# PRoMo_Base_DIP_v1_1.net
KiCad netlist of a schematic drawn in EAGLE
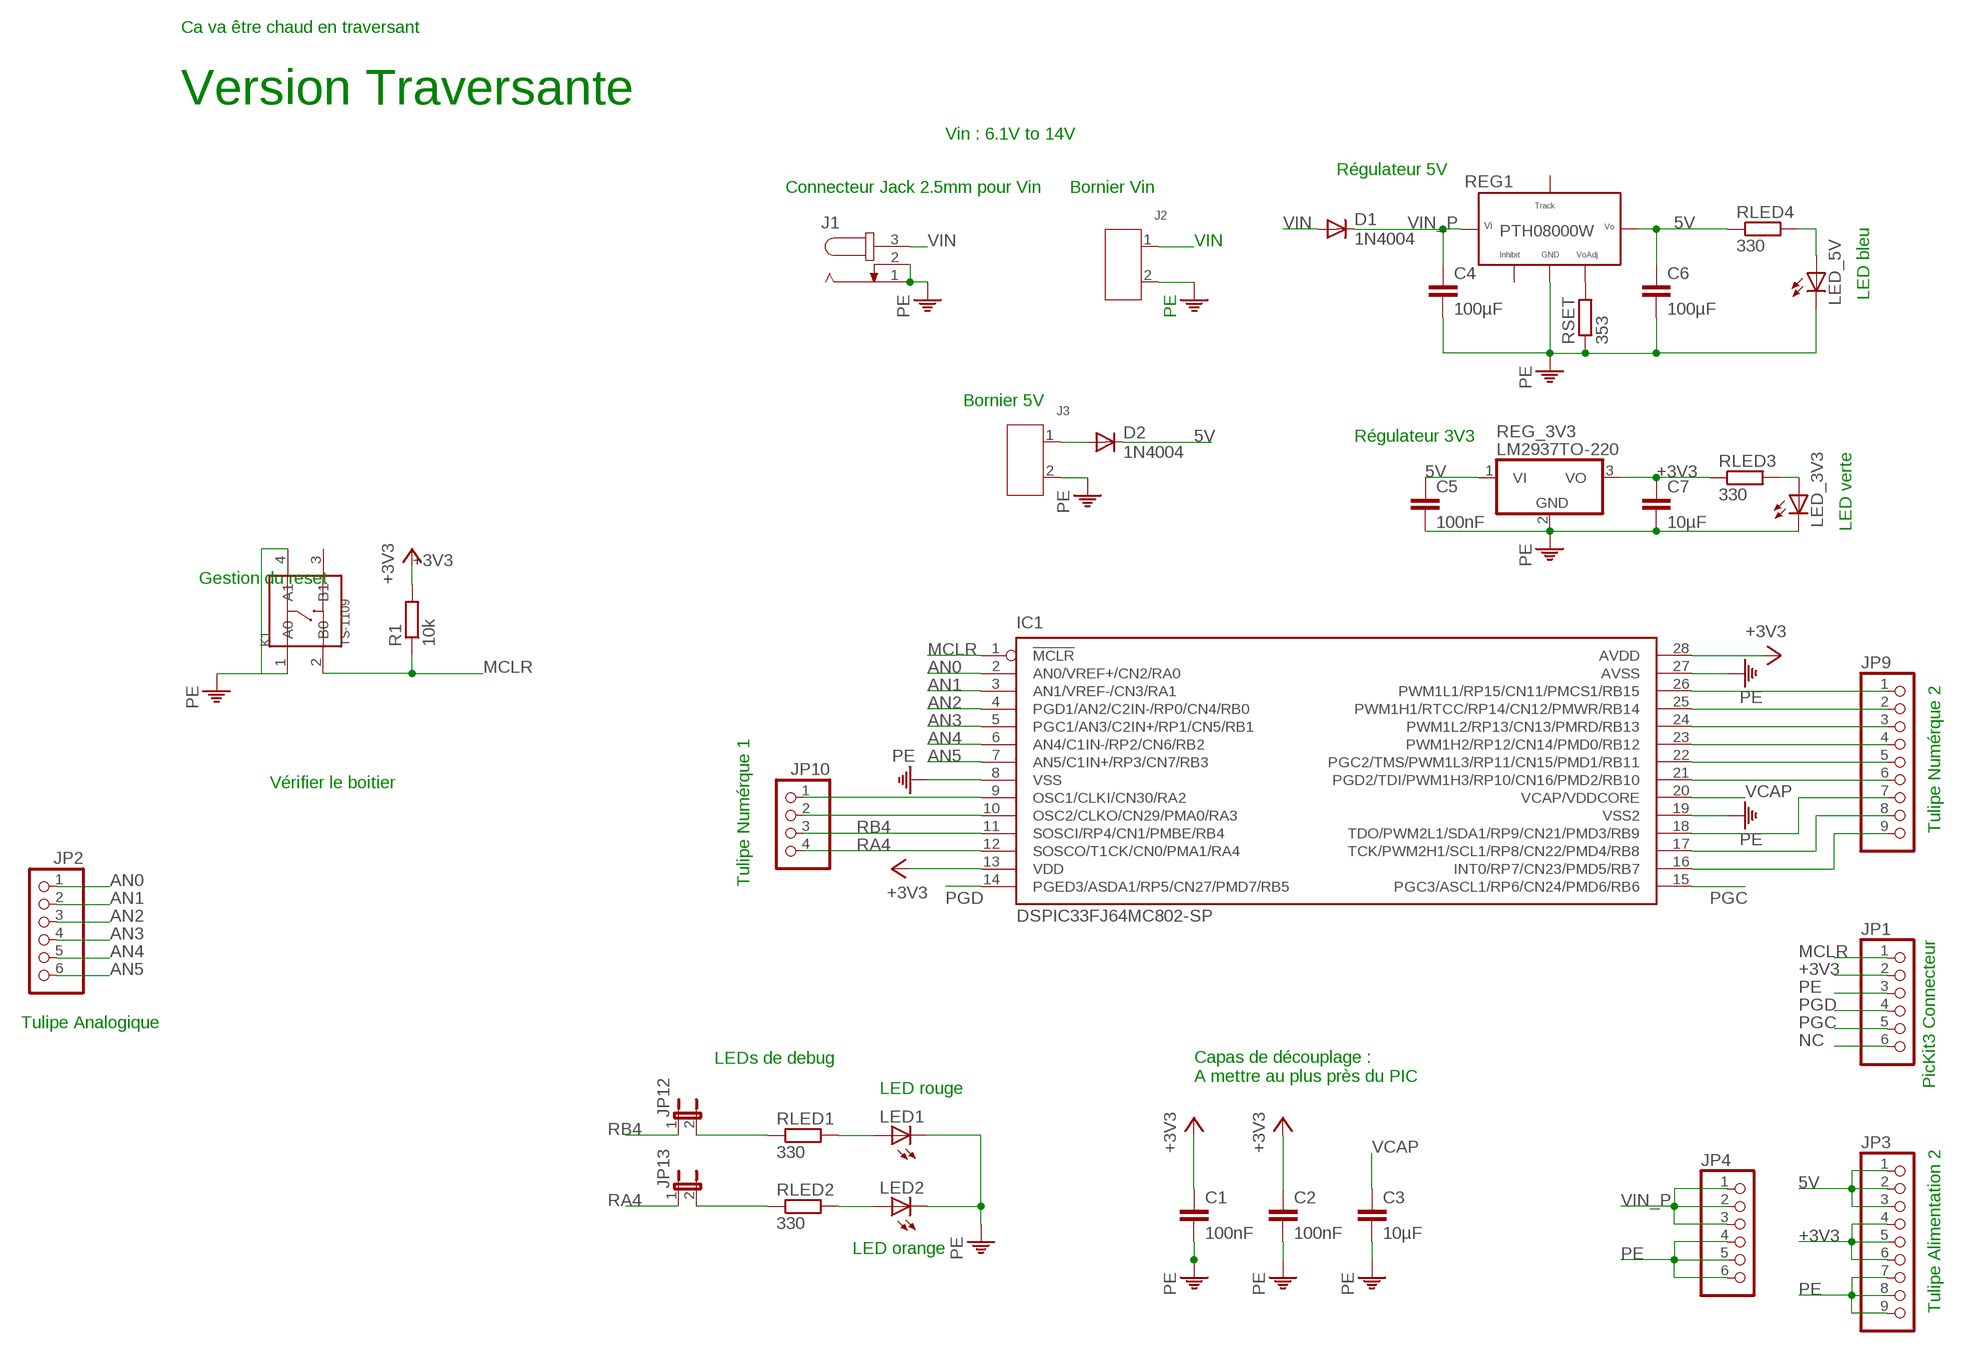
[diagram p0: schematic, sheet 1]

(export (version "E")
  (design (tool "Eeschema 10.0.6"))
  (components
    (comp (ref "C1")
      (value "100nF")
      (footprint "eagle-import:C102-043X133")
      (libsource (lib "eagle-import") (part "C-EU102-043X133"))
    )
    (comp (ref "C2")
      (value "100nF")
      (footprint "eagle-import:C050-035X075")
      (libsource (lib "eagle-import") (part "C-EU050-035X075"))
    )
    (comp (ref "C3")
      (value "10µF")
      (footprint "eagle-import:C050-035X075")
      (libsource (lib "eagle-import") (part "C-EU050-035X075"))
    )
    (comp (ref "C4")
      (value "100µF")
      (footprint "eagle-import:C050-035X075")
      (libsource (lib "eagle-import") (part "C-EU050-035X075"))
    )
    (comp (ref "C5")
      (value "100nF")
      (footprint "eagle-import:C050-035X075")
      (libsource (lib "eagle-import") (part "C-EU050-035X075"))
    )
    (comp (ref "C6")
      (value "100µF")
      (footprint "eagle-import:C050-035X075")
      (libsource (lib "eagle-import") (part "C-EU050-035X075"))
    )
    (comp (ref "C7")
      (value "10µF")
      (footprint "eagle-import:C050-035X075")
      (libsource (lib "eagle-import") (part "C-EU050-035X075"))
    )
    (comp (ref "D1")
      (value "1N4004")
      (footprint "eagle-import:DO41-10")
      (libsource (lib "eagle-import") (part "1N4004"))
    )
    (comp (ref "D2")
      (value "1N4004")
      (footprint "eagle-import:DO41-10")
      (libsource (lib "eagle-import") (part "1N4004"))
    )
    (comp (ref "IC1")
      (value "DSPIC33FJ64MC802-SP")
      (footprint "eagle-import:DIL28-3")
      (libsource (lib "eagle-import") (part "DSPIC33FJ64MC802-SP"))
    )
    (comp (ref "J1")
      (value "JACK-PLUG1")
      (footprint "eagle-import:SPC4078")
      (libsource (lib "eagle-import") (part "JACK-PLUG1"))
    )
    (comp (ref "J2")
      (value "SCREW-TERMINAL-GREEN(2P-5.0)")
      (footprint "eagle-import:H2-5.0-10.5X8.0MM")
      (libsource (lib "eagle-import") (part "SCREW-TERMINAL-GREEN(2P-5.0)"))
    )
    (comp (ref "J3")
      (value "SCREW-TERMINAL-GREEN(2P-5.0)")
      (footprint "eagle-import:H2-5.0-10.5X8.0MM")
      (libsource (lib "eagle-import") (part "SCREW-TERMINAL-GREEN(2P-5.0)"))
    )
    (comp (ref "JP1")
      (value "PINHD-1X6/90")
      (footprint "eagle-import:1X06_90")
      (libsource (lib "eagle-import") (part "PINHD-1X6/90"))
    )
    (comp (ref "JP2")
      (value "PINHD-1X6")
      (footprint "eagle-import:1X06")
      (libsource (lib "eagle-import") (part "PINHD-1X6"))
    )
    (comp (ref "JP3")
      (value "PINHD-1X9")
      (footprint "eagle-import:1X09")
      (libsource (lib "eagle-import") (part "PINHD-1X9"))
    )
    (comp (ref "JP4")
      (value "PINHD-1X6")
      (footprint "eagle-import:1X06")
      (libsource (lib "eagle-import") (part "PINHD-1X6"))
    )
    (comp (ref "JP9")
      (value "PINHD-1X9")
      (footprint "eagle-import:1X09")
      (libsource (lib "eagle-import") (part "PINHD-1X9"))
    )
    (comp (ref "JP10")
      (value "PINHD-1X4")
      (footprint "eagle-import:1X04")
      (libsource (lib "eagle-import") (part "PINHD-1X4"))
    )
    (comp (ref "JP12")
      (value "JP1E")
      (footprint "eagle-import:JP1")
      (libsource (lib "eagle-import") (part "JP1E"))
    )
    (comp (ref "JP13")
      (value "JP1E")
      (footprint "eagle-import:JP1")
      (libsource (lib "eagle-import") (part "JP1E"))
    )
    (comp (ref "K1")
      (value "TS-1109")
      (footprint "eagle-import:SW4-6.0X6.0X5.0MM")
      (libsource (lib "eagle-import") (part "DIP-BUTTON-4P"))
    )
    (comp (ref "LED1")
      (value "LED3MM")
      (footprint "eagle-import:LED3MM")
      (libsource (lib "eagle-import") (part "LED3MM"))
    )
    (comp (ref "LED2")
      (value "LED3MM")
      (footprint "eagle-import:LED3MM")
      (libsource (lib "eagle-import") (part "LED3MM"))
    )
    (comp (ref "LED_3V3")
      (value "LED3MM")
      (footprint "eagle-import:LED3MM")
      (libsource (lib "eagle-import") (part "LED3MM"))
    )
    (comp (ref "LED_5V")
      (value "LED3MM")
      (footprint "eagle-import:LED3MM")
      (libsource (lib "eagle-import") (part "LED3MM"))
    )
    (comp (ref "R1")
      (value "10k")
      (footprint "eagle-import:0207_10")
      (libsource (lib "eagle-import") (part "R-EU_0207/10"))
    )
    (comp (ref "REG1")
      (value "PTH08000W(EUS)")
      (footprint "eagle-import:TRHOUGH_HOLE_(EUS)")
      (libsource (lib "eagle-import") (part "PTH08000W(EUS)"))
    )
    (comp (ref "REG_3V3")
      (value "LM2937TO-220")
      (footprint "eagle-import:TO220V")
      (libsource (lib "eagle-import") (part "LM2937TO-220"))
    )
    (comp (ref "RLED1")
      (value "330")
      (footprint "eagle-import:0207_10")
      (libsource (lib "eagle-import") (part "R-EU_0207/10"))
    )
    (comp (ref "RLED2")
      (value "330")
      (footprint "eagle-import:0207_10")
      (libsource (lib "eagle-import") (part "R-EU_0207/10"))
    )
    (comp (ref "RLED3")
      (value "330")
      (footprint "eagle-import:0207_10")
      (libsource (lib "eagle-import") (part "R-EU_0207/10"))
    )
    (comp (ref "RLED4")
      (value "330")
      (footprint "eagle-import:0207_10")
      (libsource (lib "eagle-import") (part "R-EU_0207/10"))
    )
    (comp (ref "RSET")
      (value "353")
      (footprint "eagle-import:0207_10")
      (libsource (lib "eagle-import") (part "R-EU_0207/10"))
    )
  )
  (nets
    (net (code "1") (name "+3V3") (class "Default")
      (node (ref "C1") (pin "1") (pinfunction "1_1") (pintype "passive"))
      (node (ref "C2") (pin "1") (pinfunction "1_1") (pintype "passive"))
      (node (ref "C7") (pin "1") (pinfunction "1_1") (pintype "passive"))
      (node (ref "IC1") (pin "13") (pinfunction "VDD_13") (pintype "power_in"))
      (node (ref "IC1") (pin "28") (pinfunction "AVDD_28") (pintype "power_in"))
      (node (ref "JP1") (pin "2") (pinfunction "2_2") (pintype "passive"))
      (node (ref "JP3") (pin "4") (pinfunction "4_4") (pintype "passive"))
      (node (ref "JP3") (pin "5") (pinfunction "5_5") (pintype "passive"))
      (node (ref "JP3") (pin "6") (pinfunction "6_6") (pintype "passive"))
      (node (ref "R1") (pin "2") (pinfunction "2_2") (pintype "passive"))
      (node (ref "REG_3V3") (pin "3") (pinfunction "VO_3") (pintype "passive"))
      (node (ref "RLED3") (pin "1") (pinfunction "1_1") (pintype "passive"))
    )
    (net (code "2") (name "/5V") (class "Default")
      (node (ref "C5") (pin "1") (pinfunction "1_1") (pintype "passive"))
      (node (ref "C6") (pin "1") (pinfunction "1_1") (pintype "passive"))
      (node (ref "D2") (pin "C") (pinfunction "C_C") (pintype "passive"))
      (node (ref "JP3") (pin "1") (pinfunction "1_1") (pintype "passive"))
      (node (ref "JP3") (pin "2") (pinfunction "2_2") (pintype "passive"))
      (node (ref "JP3") (pin "3") (pinfunction "3_3") (pintype "passive"))
      (node (ref "REG1") (pin "6") (pinfunction "6_6") (pintype "bidirectional"))
      (node (ref "REG_3V3") (pin "1") (pinfunction "VI_1") (pintype "input"))
      (node (ref "RLED4") (pin "1") (pinfunction "1_1") (pintype "passive"))
    )
    (net (code "3") (name "/AN0") (class "Default")
      (node (ref "IC1") (pin "2") (pinfunction "AN0/VREF+/CN2/RA0_2") (pintype "bidirectional"))
      (node (ref "JP2") (pin "1") (pinfunction "1_1") (pintype "passive"))
    )
    (net (code "4") (name "/AN1") (class "Default")
      (node (ref "IC1") (pin "3") (pinfunction "AN1/VREF-/CN3/RA1_3") (pintype "bidirectional"))
      (node (ref "JP2") (pin "2") (pinfunction "2_2") (pintype "passive"))
    )
    (net (code "5") (name "/AN2") (class "Default")
      (node (ref "IC1") (pin "4") (pinfunction "PGD1/AN2/C2IN-/RP0/CN4/RB0_4") (pintype "bidirectional"))
      (node (ref "JP2") (pin "3") (pinfunction "3_3") (pintype "passive"))
    )
    (net (code "6") (name "/AN3") (class "Default")
      (node (ref "IC1") (pin "5") (pinfunction "PGC1/AN3/C2IN+/RP1/CN5/RB1_5") (pintype "bidirectional"))
      (node (ref "JP2") (pin "4") (pinfunction "4_4") (pintype "passive"))
    )
    (net (code "7") (name "/AN4") (class "Default")
      (node (ref "IC1") (pin "6") (pinfunction "AN4/C1IN-/RP2/CN6/RB2_6") (pintype "bidirectional"))
      (node (ref "JP2") (pin "5") (pinfunction "5_5") (pintype "passive"))
    )
    (net (code "8") (name "/AN5") (class "Default")
      (node (ref "IC1") (pin "7") (pinfunction "AN5/C1IN+/RP3/CN7/RB3_7") (pintype "bidirectional"))
      (node (ref "JP2") (pin "6") (pinfunction "6_6") (pintype "passive"))
    )
    (net (code "9") (name "/MCLR") (class "Default")
      (node (ref "IC1") (pin "1") (pinfunction "~{MCLR}_1") (pintype "input"))
      (node (ref "JP1") (pin "1") (pinfunction "1_1") (pintype "passive"))
      (node (ref "K1") (pin "2") (pinfunction "B0_2") (pintype "bidirectional"))
      (node (ref "R1") (pin "1") (pinfunction "1_1") (pintype "passive"))
    )
    (net (code "10") (name "/NC") (class "Default")
      (node (ref "JP1") (pin "6") (pinfunction "6_6") (pintype "passive"))
    )
    (net (code "11") (name "/PGC") (class "Default")
      (node (ref "IC1") (pin "15") (pinfunction "PGC3/ASCL1/RP6/CN24/PMD6/RB6_15") (pintype "bidirectional"))
      (node (ref "JP1") (pin "5") (pinfunction "5_5") (pintype "passive"))
    )
    (net (code "12") (name "/PGD") (class "Default")
      (node (ref "IC1") (pin "14") (pinfunction "PGED3/ASDA1/RP5/CN27/PMD7/RB5_14") (pintype "bidirectional"))
      (node (ref "JP1") (pin "4") (pinfunction "4_4") (pintype "passive"))
    )
    (net (code "13") (name "/RA4") (class "Default")
      (node (ref "IC1") (pin "12") (pinfunction "SOSCO/T1CK/CN0/PMA1/RA4_12") (pintype "bidirectional"))
      (node (ref "JP10") (pin "4") (pinfunction "4_4") (pintype "passive"))
      (node (ref "JP13") (pin "1") (pinfunction "1_1") (pintype "passive"))
    )
    (net (code "14") (name "/RB4") (class "Default")
      (node (ref "IC1") (pin "11") (pinfunction "SOSCI/RP4/CN1/PMBE/RB4_11") (pintype "bidirectional"))
      (node (ref "JP10") (pin "3") (pinfunction "3_3") (pintype "passive"))
      (node (ref "JP12") (pin "1") (pinfunction "1_1") (pintype "passive"))
    )
    (net (code "15") (name "/VCAP") (class "Default")
      (node (ref "C3") (pin "1") (pinfunction "1_1") (pintype "passive"))
      (node (ref "IC1") (pin "20") (pinfunction "VCAP/VDDCORE_20") (pintype "power_in"))
    )
    (net (code "16") (name "/VIN") (class "Default")
      (node (ref "D1") (pin "A") (pinfunction "A_A") (pintype "passive"))
      (node (ref "J1") (pin "3") (pinfunction "3_3") (pintype "passive"))
      (node (ref "J2") (pin "1") (pinfunction "1_1") (pintype "bidirectional"))
    )
    (net (code "17") (name "/VIN_P") (class "Default")
      (node (ref "C4") (pin "1") (pinfunction "1_1") (pintype "passive"))
      (node (ref "D1") (pin "C") (pinfunction "C_C") (pintype "passive"))
      (node (ref "JP4") (pin "1") (pinfunction "1_1") (pintype "passive"))
      (node (ref "JP4") (pin "2") (pinfunction "2_2") (pintype "passive"))
      (node (ref "JP4") (pin "3") (pinfunction "3_3") (pintype "passive"))
      (node (ref "REG1") (pin "3") (pinfunction "3_3") (pintype "bidirectional"))
    )
    (net (code "18") (name "Net-(D2-PadA)") (class "Default")
      (node (ref "D2") (pin "A") (pinfunction "A_A") (pintype "passive"))
      (node (ref "J3") (pin "1") (pinfunction "1_1") (pintype "bidirectional"))
    )
    (net (code "19") (name "Net-(IC1-INT0{slash}RP7{slash}CN23{slash}PMD5{slash}RB7)") (class "Default")
      (node (ref "IC1") (pin "16") (pinfunction "INT0/RP7/CN23/PMD5/RB7_16") (pintype "bidirectional"))
      (node (ref "JP9") (pin "9") (pinfunction "9_9") (pintype "passive"))
    )
    (net (code "20") (name "Net-(IC1-OSC1{slash}CLKI{slash}CN30{slash}RA2)") (class "Default")
      (node (ref "IC1") (pin "9") (pinfunction "OSC1/CLKI/CN30/RA2_9") (pintype "bidirectional"))
      (node (ref "JP10") (pin "1") (pinfunction "1_1") (pintype "passive"))
    )
    (net (code "21") (name "Net-(IC1-OSC2{slash}CLKO{slash}CN29{slash}PMA0{slash}RA3)") (class "Default")
      (node (ref "IC1") (pin "10") (pinfunction "OSC2/CLKO/CN29/PMA0/RA3_10") (pintype "bidirectional"))
      (node (ref "JP10") (pin "2") (pinfunction "2_2") (pintype "passive"))
    )
    (net (code "22") (name "Net-(IC1-PGC2{slash}TMS{slash}PWM1L3{slash}RP11{slash}CN15{slash}PMD1{slash}RB11)") (class "Default")
      (node (ref "IC1") (pin "22") (pinfunction "PGC2/TMS/PWM1L3/RP11/CN15/PMD1/RB11_22") (pintype "bidirectional"))
      (node (ref "JP9") (pin "5") (pinfunction "5_5") (pintype "passive"))
    )
    (net (code "23") (name "Net-(IC1-PGD2{slash}TDI{slash}PWM1H3{slash}RP10{slash}CN16{slash}PMD2{slash}RB10)") (class "Default")
      (node (ref "IC1") (pin "21") (pinfunction "PGD2/TDI/PWM1H3/RP10/CN16/PMD2/RB10_21") (pintype "bidirectional"))
      (node (ref "JP9") (pin "6") (pinfunction "6_6") (pintype "passive"))
    )
    (net (code "24") (name "Net-(IC1-PWM1H1{slash}RTCC{slash}RP14{slash}CN12{slash}PMWR{slash}RB14)") (class "Default")
      (node (ref "IC1") (pin "25") (pinfunction "PWM1H1/RTCC/RP14/CN12/PMWR/RB14_25") (pintype "bidirectional"))
      (node (ref "JP9") (pin "2") (pinfunction "2_2") (pintype "passive"))
    )
    (net (code "25") (name "Net-(IC1-PWM1H2{slash}RP12{slash}CN14{slash}PMD0{slash}RB12)") (class "Default")
      (node (ref "IC1") (pin "23") (pinfunction "PWM1H2/RP12/CN14/PMD0/RB12_23") (pintype "bidirectional"))
      (node (ref "JP9") (pin "4") (pinfunction "4_4") (pintype "passive"))
    )
    (net (code "26") (name "Net-(IC1-PWM1L1{slash}RP15{slash}CN11{slash}PMCS1{slash}RB15)") (class "Default")
      (node (ref "IC1") (pin "26") (pinfunction "PWM1L1/RP15/CN11/PMCS1/RB15_26") (pintype "bidirectional"))
      (node (ref "JP9") (pin "1") (pinfunction "1_1") (pintype "passive"))
    )
    (net (code "27") (name "Net-(IC1-PWM1L2{slash}RP13{slash}CN13{slash}PMRD{slash}RB13)") (class "Default")
      (node (ref "IC1") (pin "24") (pinfunction "PWM1L2/RP13/CN13/PMRD/RB13_24") (pintype "bidirectional"))
      (node (ref "JP9") (pin "3") (pinfunction "3_3") (pintype "passive"))
    )
    (net (code "28") (name "Net-(IC1-TCK{slash}PWM2H1{slash}SCL1{slash}RP8{slash}CN22{slash}PMD4{slash}RB8)") (class "Default")
      (node (ref "IC1") (pin "17") (pinfunction "TCK/PWM2H1/SCL1/RP8/CN22/PMD4/RB8_17") (pintype "bidirectional"))
      (node (ref "JP9") (pin "8") (pinfunction "8_8") (pintype "passive"))
    )
    (net (code "29") (name "Net-(IC1-TDO{slash}PWM2L1{slash}SDA1{slash}RP9{slash}CN21{slash}PMD3{slash}RB9)") (class "Default")
      (node (ref "IC1") (pin "18") (pinfunction "TDO/PWM2L1/SDA1/RP9/CN21/PMD3/RB9_18") (pintype "bidirectional"))
      (node (ref "JP9") (pin "7") (pinfunction "7_7") (pintype "passive"))
    )
    (net (code "30") (name "Net-(JP12-Pad2)") (class "Default")
      (node (ref "JP12") (pin "2") (pinfunction "2_2") (pintype "passive"))
      (node (ref "RLED1") (pin "1") (pinfunction "1_1") (pintype "passive"))
    )
    (net (code "31") (name "Net-(JP13-Pad2)") (class "Default")
      (node (ref "JP13") (pin "2") (pinfunction "2_2") (pintype "passive"))
      (node (ref "RLED2") (pin "1") (pinfunction "1_1") (pintype "passive"))
    )
    (net (code "32") (name "Net-(LED1-PadA)") (class "Default")
      (node (ref "LED1") (pin "A") (pinfunction "A_A") (pintype "passive"))
      (node (ref "RLED1") (pin "2") (pinfunction "2_2") (pintype "passive"))
    )
    (net (code "33") (name "Net-(LED2-PadA)") (class "Default")
      (node (ref "LED2") (pin "A") (pinfunction "A_A") (pintype "passive"))
      (node (ref "RLED2") (pin "2") (pinfunction "2_2") (pintype "passive"))
    )
    (net (code "34") (name "Net-(LED_3V3-PadA)") (class "Default")
      (node (ref "LED_3V3") (pin "A") (pinfunction "A_A") (pintype "passive"))
      (node (ref "RLED3") (pin "2") (pinfunction "2_2") (pintype "passive"))
    )
    (net (code "35") (name "Net-(LED_5V-PadA)") (class "Default")
      (node (ref "LED_5V") (pin "A") (pinfunction "A_A") (pintype "passive"))
      (node (ref "RLED4") (pin "2") (pinfunction "2_2") (pintype "passive"))
    )
    (net (code "36") (name "Net-(REG1-Pad5)") (class "Default")
      (node (ref "REG1") (pin "5") (pinfunction "5_5") (pintype "bidirectional"))
      (node (ref "RSET") (pin "2") (pinfunction "2_2") (pintype "passive"))
    )
    (net (code "37") (name "PE") (class "Default")
      (node (ref "C1") (pin "2") (pinfunction "2_2") (pintype "passive"))
      (node (ref "C2") (pin "2") (pinfunction "2_2") (pintype "passive"))
      (node (ref "C3") (pin "2") (pinfunction "2_2") (pintype "passive"))
      (node (ref "C4") (pin "2") (pinfunction "2_2") (pintype "passive"))
      (node (ref "C5") (pin "2") (pinfunction "2_2") (pintype "passive"))
      (node (ref "C6") (pin "2") (pinfunction "2_2") (pintype "passive"))
      (node (ref "C7") (pin "2") (pinfunction "2_2") (pintype "passive"))
      (node (ref "IC1") (pin "19") (pinfunction "VSS2_19") (pintype "power_in"))
      (node (ref "IC1") (pin "27") (pinfunction "AVSS_27") (pintype "power_in"))
      (node (ref "IC1") (pin "8") (pinfunction "VSS_8") (pintype "power_in"))
      (node (ref "J1") (pin "1") (pinfunction "1_1") (pintype "passive"))
      (node (ref "J1") (pin "2") (pinfunction "2_2") (pintype "passive"))
      (node (ref "J2") (pin "2") (pinfunction "2_2") (pintype "bidirectional"))
      (node (ref "J3") (pin "2") (pinfunction "2_2") (pintype "bidirectional"))
      (node (ref "JP1") (pin "3") (pinfunction "3_3") (pintype "passive"))
      (node (ref "JP3") (pin "7") (pinfunction "7_7") (pintype "passive"))
      (node (ref "JP3") (pin "8") (pinfunction "8_8") (pintype "passive"))
      (node (ref "JP3") (pin "9") (pinfunction "9_9") (pintype "passive"))
      (node (ref "JP4") (pin "4") (pinfunction "4_4") (pintype "passive"))
      (node (ref "JP4") (pin "5") (pinfunction "5_5") (pintype "passive"))
      (node (ref "JP4") (pin "6") (pinfunction "6_6") (pintype "passive"))
      (node (ref "K1") (pin "1") (pinfunction "A0_1") (pintype "bidirectional"))
      (node (ref "K1") (pin "4") (pinfunction "A1_4") (pintype "bidirectional"))
      (node (ref "LED1") (pin "K") (pinfunction "C_K") (pintype "passive"))
      (node (ref "LED2") (pin "K") (pinfunction "C_K") (pintype "passive"))
      (node (ref "LED_3V3") (pin "K") (pinfunction "C_K") (pintype "passive"))
      (node (ref "LED_5V") (pin "K") (pinfunction "C_K") (pintype "passive"))
      (node (ref "REG1") (pin "1") (pinfunction "1_1") (pintype "bidirectional"))
      (node (ref "REG_3V3") (pin "2") (pinfunction "GND_2") (pintype "passive"))
      (node (ref "RSET") (pin "1") (pinfunction "1_1") (pintype "passive"))
    )
    (net (code "38") (name "unconnected-(K1-B1-Pad3)") (class "Default")
      (node (ref "K1") (pin "3") (pinfunction "B1_3") (pintype "bidirectional"))
    )
    (net (code "39") (name "unconnected-(REG1-Pad2)") (class "Default")
      (node (ref "REG1") (pin "2") (pinfunction "2_2") (pintype "bidirectional"))
    )
    (net (code "40") (name "unconnected-(REG1-Pad4)") (class "Default")
      (node (ref "REG1") (pin "4") (pinfunction "4_4") (pintype "bidirectional"))
    )
  )
)
